# Phototransistor_Board.net
KiCad netlist of a schematic drawn in Altium Designer
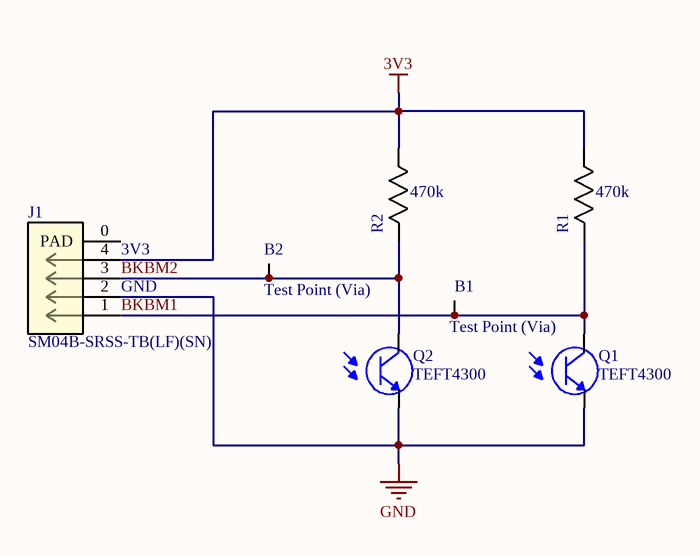
[diagram p0: Phototransistor Board.SchDoc]

(export (version "E")
  (design (tool "Eeschema 10.0.6"))
  (components
    (comp (ref "B1")
      (value "Test Point (Via)")
      (footprint "TP")
      (libsource (lib "IC_Library") (part "Test Point (Via)"))
    )
    (comp (ref "B2")
      (value "Test Point (Via)")
      (footprint "TP")
      (libsource (lib "IC_Library") (part "Test Point (Via)"))
    )
    (comp (ref "J1")
      (value "SM04B-SRSS-TB(LF)(SN)")
      (footprint "CONN_SM04B_JST")
      (description "CONN HEADER SMD R/A 4POS 1MM")
      (fields
        (field (name "PART NUMBER") "CN HDR 4POS JST SH_SR")
        (field (name "COPYRIGHT") "Copyright (C) 2023 Ultra Librarian. All rights reserved.")
      )
      (libsource (lib "Connector_Library") (part "CN HDR 4POS JST SH_SR"))
    )
    (comp (ref "Q1")
      (value "TEFT4300")
      (footprint "IRLEDFOOTPRINT")
      (description "Phototransistor 925nm Top View Radial, 3mm Dia _T-1_")
      (fields (field (name "MF") "Vishay Semiconductor"))
      (libsource (lib "Transistor_Library") (part "TEFT4300"))
    )
    (comp (ref "Q2")
      (value "TEFT4300")
      (footprint "IRLEDFOOTPRINT")
      (description "Phototransistor 925nm Top View Radial, 3mm Dia _T-1_")
      (fields (field (name "MF") "Vishay Semiconductor"))
      (libsource (lib "Transistor_Library") (part "TEFT4300"))
    )
    (comp (ref "R1")
      (value "470k")
      (footprint "0603")
      (description "Default Resistor Symbol")
      (fields (field (name "TOLERANCE") "5%") (field (name "PART NUMBER") "RES 470k 1/8W"))
      (libsource (lib "") (part "RES_DEFAULT_1"))
    )
    (comp (ref "R2")
      (value "470k")
      (footprint "0603")
      (description "Default Resistor Symbol")
      (fields (field (name "TOLERANCE") "5%") (field (name "PART NUMBER") "RES 470k 1/8W"))
      (libsource (lib "Resistor_Library") (part "RES_DEFAULT"))
    )
  )
  (nets
    (net (code "1") (name "/BKBM1") (class "Default")
      (node (ref "B1") (pin "1") (pinfunction "1_1") (pintype "passive"))
      (node (ref "J1") (pin "1") (pinfunction "1_1") (pintype "passive"))
      (node (ref "Q1") (pin "C") (pinfunction "C_C") (pintype "passive"))
      (node (ref "R1") (pin "2") (pinfunction "R2_2") (pintype "passive"))
    )
    (net (code "2") (name "/BKBM2") (class "Default")
      (node (ref "B2") (pin "1") (pinfunction "1_1") (pintype "passive"))
      (node (ref "J1") (pin "3") (pinfunction "3_3") (pintype "passive"))
      (node (ref "Q2") (pin "C") (pinfunction "C_C") (pintype "passive"))
      (node (ref "R2") (pin "2") (pinfunction "R2_2") (pintype "passive"))
    )
    (net (code "3") (name "3V3") (class "Default")
      (node (ref "J1") (pin "4") (pinfunction "4_4") (pintype "passive"))
      (node (ref "R1") (pin "1") (pinfunction "R1_1") (pintype "passive"))
      (node (ref "R2") (pin "1") (pinfunction "R1_1") (pintype "passive"))
    )
    (net (code "4") (name "GND") (class "Default")
      (node (ref "J1") (pin "2") (pinfunction "2_2") (pintype "passive"))
      (node (ref "Q1") (pin "E") (pinfunction "E_E") (pintype "passive"))
      (node (ref "Q2") (pin "E") (pinfunction "E_E") (pintype "passive"))
    )
    (net (code "5") (name "unconnected-(J1-PAD-Pad0)") (class "Default")
      (node (ref "J1") (pin "0") (pinfunction "PAD_0") (pintype "passive"))
    )
  )
)
